# 03-USER_IO_STATUS.net
KiCad netlist of a schematic drawn in Altium Designer
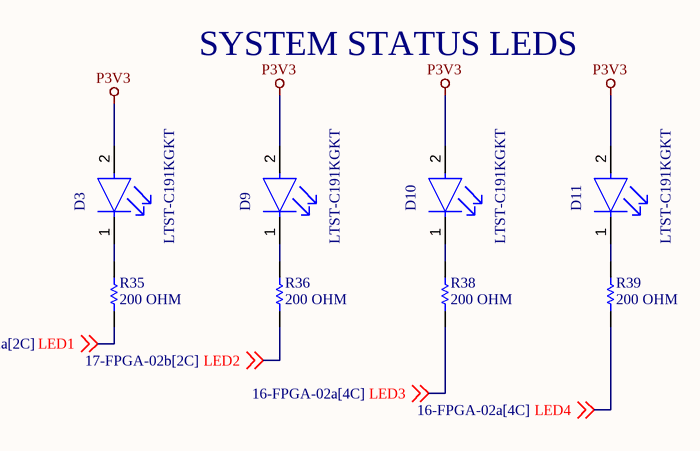
[diagram p0: 03-USER_IO_STATUS.SchDoc]

(export (version "E")
  (design (tool "Eeschema 10.0.6"))
  (components
    (comp (ref "D3")
      (value "LTST-C191KGKT")
      (footprint "FP-LTST-C191KGKT-MFG")
      (description "LED GREEN CLEAR SMD")
      (libsource (lib "Altium Content Vault") (part "8706943c75ba83719d021d2fdc84c58"))
    )
    (comp (ref "D9")
      (value "LTST-C191KGKT")
      (footprint "FP-LTST-C191KGKT-MFG")
      (description "LED GREEN CLEAR SMD")
      (libsource (lib "Altium Content Vault") (part "8706943c75ba83719d021d2fdc84c58"))
    )
    (comp (ref "D10")
      (value "LTST-C191KGKT")
      (footprint "FP-LTST-C191KGKT-MFG")
      (description "LED GREEN CLEAR SMD")
      (libsource (lib "Altium Content Vault") (part "8706943c75ba83719d021d2fdc84c58"))
    )
    (comp (ref "D11")
      (value "LTST-C191KGKT")
      (footprint "FP-LTST-C191KGKT-MFG")
      (description "LED GREEN CLEAR SMD")
      (libsource (lib "Altium Content Vault") (part "8706943c75ba83719d021d2fdc84c58"))
    )
    (comp (ref "R35")
      (value "200 OHM")
      (footprint "RESC1608X55X30NL15T15")
      (description "ERJ-3EKF2000V")
      (fields (field (name "MANUFACTURER") "Panasonic"))
      (libsource (lib "Altium Content Vault") (part "RES"))
    )
    (comp (ref "R36")
      (value "200 OHM")
      (footprint "RESC1608X55X30NL15T15")
      (description "ERJ-3EKF2000V")
      (fields (field (name "MANUFACTURER") "Panasonic"))
      (libsource (lib "Altium Content Vault") (part "RES"))
    )
    (comp (ref "R38")
      (value "200 OHM")
      (footprint "RESC1608X55X30NL15T15")
      (description "ERJ-3EKF2000V")
      (fields (field (name "MANUFACTURER") "Panasonic"))
      (libsource (lib "Altium Content Vault") (part "RES"))
    )
    (comp (ref "R39")
      (value "200 OHM")
      (footprint "RESC1608X55X30NL15T15")
      (description "ERJ-3EKF2000V")
      (fields (field (name "MANUFACTURER") "Panasonic"))
      (libsource (lib "Altium Content Vault") (part "RES"))
    )
  )
  (nets
    (net (code "1") (name "LED1") (class "Default")
      (node (ref "R35") (pin "1") (pinfunction "1_1") (pintype "passive"))
    )
    (net (code "2") (name "LED2") (class "Default")
      (node (ref "R36") (pin "1") (pinfunction "1_1") (pintype "passive"))
    )
    (net (code "3") (name "LED3") (class "Default")
      (node (ref "R38") (pin "1") (pinfunction "1_1") (pintype "passive"))
    )
    (net (code "4") (name "LED4") (class "Default")
      (node (ref "R39") (pin "1") (pinfunction "1_1") (pintype "passive"))
    )
    (net (code "5") (name "Net-(D3-C)") (class "Default")
      (node (ref "D3") (pin "1") (pinfunction "C_1") (pintype "passive"))
      (node (ref "R35") (pin "2") (pinfunction "2_2") (pintype "passive"))
    )
    (net (code "6") (name "Net-(D9-C)") (class "Default")
      (node (ref "D9") (pin "1") (pinfunction "C_1") (pintype "passive"))
      (node (ref "R36") (pin "2") (pinfunction "2_2") (pintype "passive"))
    )
    (net (code "7") (name "Net-(D10-C)") (class "Default")
      (node (ref "D10") (pin "1") (pinfunction "C_1") (pintype "passive"))
      (node (ref "R38") (pin "2") (pinfunction "2_2") (pintype "passive"))
    )
    (net (code "8") (name "Net-(D11-C)") (class "Default")
      (node (ref "D11") (pin "1") (pinfunction "C_1") (pintype "passive"))
      (node (ref "R39") (pin "2") (pinfunction "2_2") (pintype "passive"))
    )
    (net (code "9") (name "P3V3") (class "Default")
      (node (ref "D10") (pin "2") (pinfunction "A_2") (pintype "passive"))
      (node (ref "D11") (pin "2") (pinfunction "A_2") (pintype "passive"))
      (node (ref "D3") (pin "2") (pinfunction "A_2") (pintype "passive"))
      (node (ref "D9") (pin "2") (pinfunction "A_2") (pintype "passive"))
    )
  )
)
